# 5_unextended_ANSI_periferals.net
KiCad netlist of a schematic drawn in Altium Designer
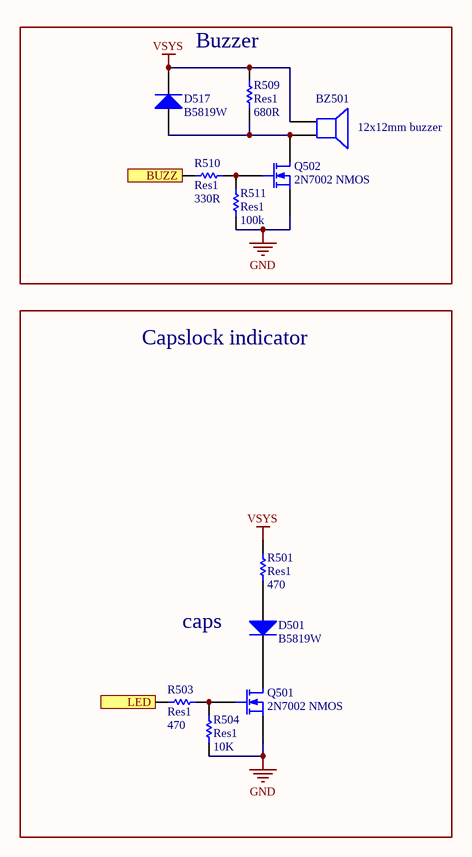
[diagram p0: 5_unextended_ANSI_periferals.SchDoc]

(export (version "E")
  (design (tool "Eeschema 10.0.6"))
  (components
    (comp (ref "BZ501")
      (value "12x12mm buzzer")
      (footprint "buzzer 12x12")
      (description "Loudspeaker")
      (fields (field (name "LCSC PART #") "C409829") (field (name "MRF.PART") "YS-SBZ1230"))
      (libsource (lib "Miscellaneous Devices") (part "Speaker"))
    )
    (comp (ref "D501")
      (value "B5819W")
      (footprint "MX-switch - CAPS - LED NO SWITCH")
      (description "Default Diode")
      (libsource (lib "Miscellaneous Devices") (part "Diode"))
    )
    (comp (ref "D517")
      (value "B5819W")
      (footprint "SOD-123")
      (description "Default Diode")
      (fields (field (name "LCSC PART #") "C8598"))
      (libsource (lib "Miscellaneous Devices") (part "Diode"))
    )
    (comp (ref "Q501")
      (value "2N7002 NMOS")
      (footprint "SOT-23-3")
      (description "N-Channel MOSFET")
      (fields (field (name "LCSC PART #") "C8545") (field (name "MRF.PART") "2N7002"))
      (libsource (lib "Miscellaneous Devices") (part "MOSFET-N"))
    )
    (comp (ref "Q502")
      (value "2N7002 NMOS")
      (footprint "SOT-23-3")
      (description "N-Channel MOSFET")
      (fields (field (name "LCSC PART #") "C8545") (field (name "MRF.PART") "2N7002"))
      (libsource (lib "Miscellaneous Devices") (part "MOSFET-N"))
    )
    (comp (ref "R501")
      (value "Res1")
      (footprint "R0603[1608]")
      (description "Resistor")
      (fields
        (field (name "ALTIUM_VALUE") "470")
        (field (name "MFG") "Panasonic Electronic Components")
        (field (name "LCSC PART #") "C23179")
      )
      (libsource (lib "Miscellaneous Devices") (part "Res1"))
    )
    (comp (ref "R503")
      (value "Res1")
      (footprint "R0603[1608]")
      (description "Resistor")
      (fields
        (field (name "ALTIUM_VALUE") "470")
        (field (name "MFG") "Panasonic Electronic Components")
        (field (name "LCSC PART #") "C23179")
      )
      (libsource (lib "Miscellaneous Devices") (part "Res1"))
    )
    (comp (ref "R504")
      (value "Res1")
      (footprint "R0603[1608]")
      (description "Resistor")
      (fields
        (field (name "ALTIUM_VALUE") "10K")
        (field (name "MFG") "Panasonic Electronic Components")
        (field (name "LCSC PART #") "C25804")
      )
      (libsource (lib "Miscellaneous Devices") (part "Res1"))
    )
    (comp (ref "R509")
      (value "Res1")
      (footprint "R0603[1608]")
      (description "Resistor")
      (fields
        (field (name "ALTIUM_VALUE") "680R")
        (field (name "MRF.PART") "0603WAF6800T5E")
        (field (name "LCSC PART #") "C23228")
      )
      (libsource (lib "Miscellaneous Devices") (part "Res1"))
    )
    (comp (ref "R510")
      (value "Res1")
      (footprint "R0603[1608]")
      (description "Resistor")
      (fields
        (field (name "ALTIUM_VALUE") "330R")
        (field (name "LCSC PART #") "C23138")
        (field (name "MRF.PART") "0603WAF3300T5E")
      )
      (libsource (lib "Miscellaneous Devices") (part "Res1"))
    )
    (comp (ref "R511")
      (value "Res1")
      (footprint "R0603[1608]")
      (description "Resistor")
      (fields
        (field (name "ALTIUM_VALUE") "100k")
        (field (name "MRF.PART") "0603WAF1003T5E")
        (field (name "LCSC PART #") "C25803")
      )
      (libsource (lib "Miscellaneous Devices") (part "Res1"))
    )
  )
  (nets
    (net (code "1") (name "/BUZZ") (class "Default")
      (node (ref "R510") (pin "2") (pinfunction "2_2") (pintype "passive"))
    )
    (net (code "2") (name "/LED") (class "Default")
      (node (ref "R503") (pin "1") (pinfunction "1_1") (pintype "passive"))
    )
    (net (code "3") (name "GND") (class "Default")
      (node (ref "Q501") (pin "2") (pinfunction "S_2") (pintype "passive"))
      (node (ref "Q502") (pin "2") (pinfunction "S_2") (pintype "passive"))
      (node (ref "R504") (pin "2") (pinfunction "2_2") (pintype "passive"))
      (node (ref "R511") (pin "2") (pinfunction "2_2") (pintype "passive"))
    )
    (net (code "4") (name "Net-(D501-A)") (class "Default")
      (node (ref "D501") (pin "1") (pinfunction "A_1") (pintype "passive"))
      (node (ref "R501") (pin "1") (pinfunction "1_1") (pintype "passive"))
    )
    (net (code "5") (name "Net-(D501-K)") (class "Default")
      (node (ref "D501") (pin "2") (pinfunction "K_2") (pintype "passive"))
      (node (ref "Q501") (pin "3") (pinfunction "D_3") (pintype "passive"))
    )
    (net (code "6") (name "Net-(D517-A)") (class "Default")
      (node (ref "BZ501") (pin "2") (pinfunction "2_2") (pintype "passive"))
      (node (ref "D517") (pin "1") (pinfunction "A_1") (pintype "passive"))
      (node (ref "Q502") (pin "3") (pinfunction "D_3") (pintype "passive"))
      (node (ref "R509") (pin "2") (pinfunction "2_2") (pintype "passive"))
    )
    (net (code "7") (name "Net-(Q501-G)") (class "Default")
      (node (ref "Q501") (pin "1") (pinfunction "G_1") (pintype "passive"))
      (node (ref "R503") (pin "2") (pinfunction "2_2") (pintype "passive"))
      (node (ref "R504") (pin "1") (pinfunction "1_1") (pintype "passive"))
    )
    (net (code "8") (name "Net-(Q502-G)") (class "Default")
      (node (ref "Q502") (pin "1") (pinfunction "G_1") (pintype "passive"))
      (node (ref "R510") (pin "1") (pinfunction "1_1") (pintype "passive"))
      (node (ref "R511") (pin "1") (pinfunction "1_1") (pintype "passive"))
    )
    (net (code "9") (name "VSYS") (class "Default")
      (node (ref "BZ501") (pin "1") (pinfunction "1_1") (pintype "passive"))
      (node (ref "D517") (pin "2") (pinfunction "K_2") (pintype "passive"))
      (node (ref "R501") (pin "2") (pinfunction "2_2") (pintype "passive"))
      (node (ref "R509") (pin "1") (pinfunction "1_1") (pintype "passive"))
    )
  )
)
